# P03_DISPLAY_TOUCH.net
KiCad netlist of a schematic drawn in EasyEDA
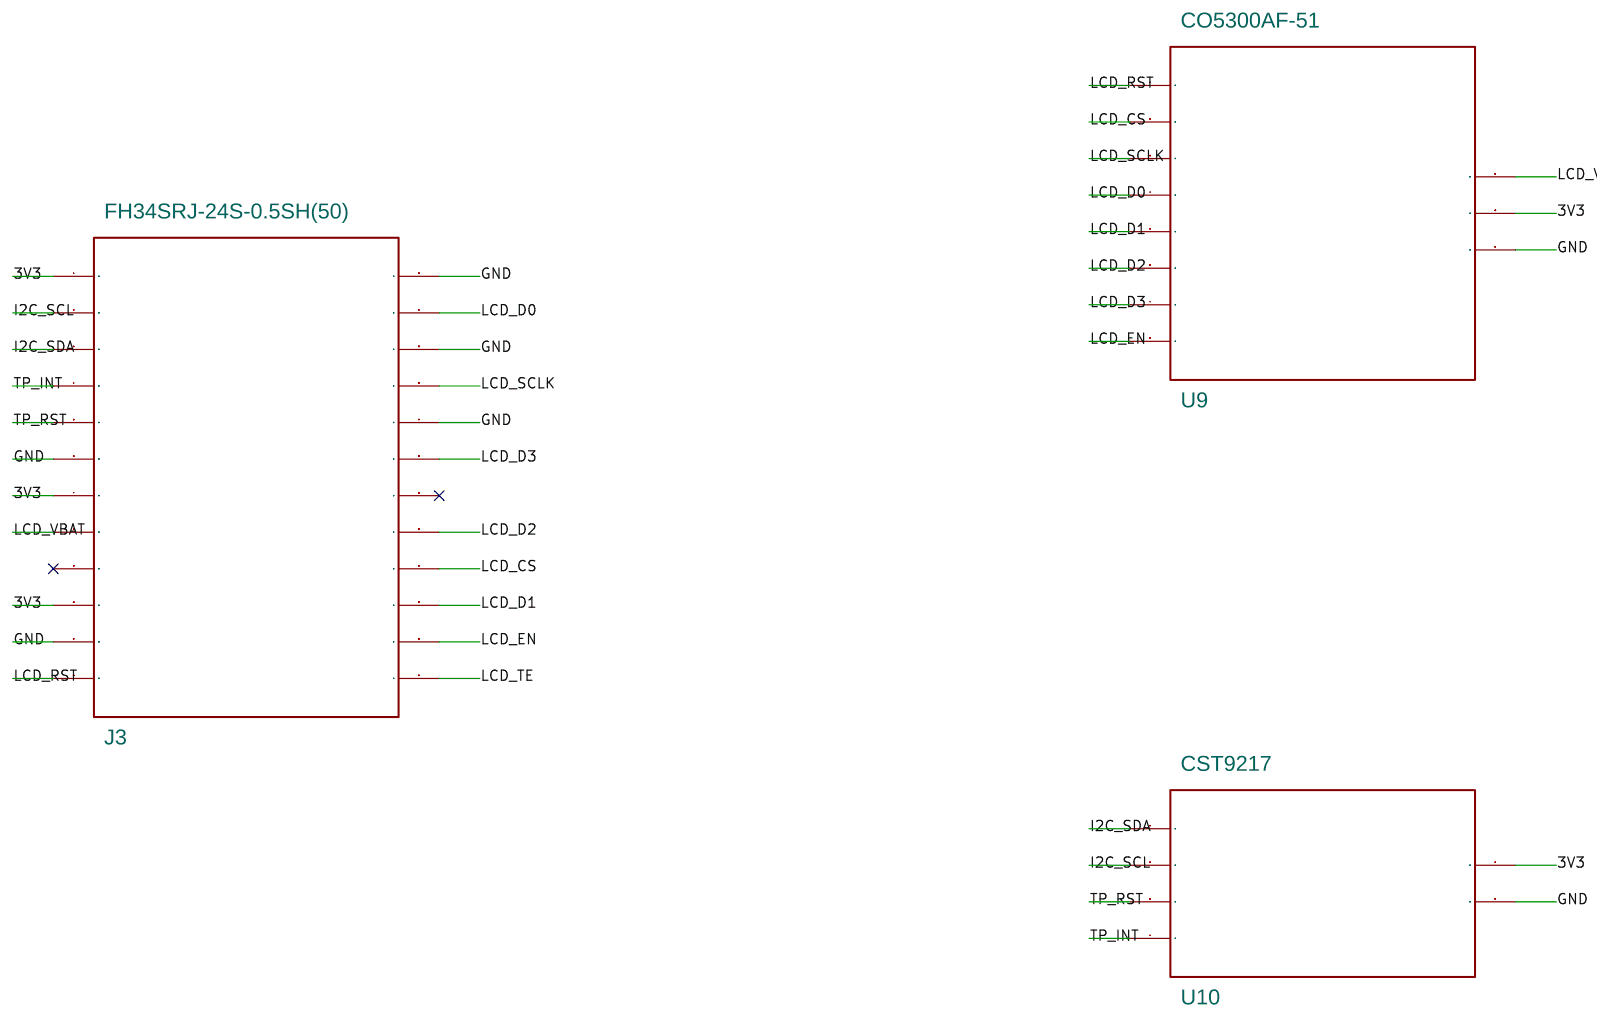
[diagram p0: schematic sheet]

(export (version "E")
  (design (tool "Eeschema 10.0.6"))
  (components
    (comp (ref "J3") (value "FH34SRJ-24S-0.5SH(50)") (libsource (lib "") (part "FPC_24P")))
    (comp (ref "U9") (value "CO5300AF-51") (libsource (lib "") (part "AMOLED_Controller")))
    (comp (ref "U10") (value "CST9217") (libsource (lib "") (part "Touch_Controller")))
  )
  (nets
    (net (code "1") (name "/3V3") (class "Default")
      (node (ref "J3") (pin "1") (pinfunction "1_1") (pintype "unspecified"))
      (node (ref "J3") (pin "10") (pinfunction "1_10") (pintype "unspecified"))
      (node (ref "J3") (pin "7") (pinfunction "1_7") (pintype "unspecified"))
      (node (ref "U10") (pin "5") (pinfunction "1_5") (pintype "unspecified"))
      (node (ref "U9") (pin "10") (pinfunction "1_10") (pintype "unspecified"))
    )
    (net (code "2") (name "/GND") (class "Default")
      (node (ref "J3") (pin "11") (pinfunction "1_11") (pintype "unspecified"))
      (node (ref "J3") (pin "13") (pinfunction "1_13") (pintype "unspecified"))
      (node (ref "J3") (pin "15") (pinfunction "1_15") (pintype "unspecified"))
      (node (ref "J3") (pin "17") (pinfunction "1_17") (pintype "unspecified"))
      (node (ref "J3") (pin "6") (pinfunction "1_6") (pintype "unspecified"))
      (node (ref "U10") (pin "6") (pinfunction "1_6") (pintype "unspecified"))
      (node (ref "U9") (pin "11") (pinfunction "1_11") (pintype "unspecified"))
    )
    (net (code "3") (name "/I2C_SCL") (class "Default")
      (node (ref "J3") (pin "2") (pinfunction "1_2") (pintype "unspecified"))
      (node (ref "U10") (pin "2") (pinfunction "1_2") (pintype "unspecified"))
    )
    (net (code "4") (name "/I2C_SDA") (class "Default")
      (node (ref "J3") (pin "3") (pinfunction "1_3") (pintype "unspecified"))
      (node (ref "U10") (pin "1") (pinfunction "1_1") (pintype "unspecified"))
    )
    (net (code "5") (name "/LCD_CS") (class "Default")
      (node (ref "J3") (pin "21") (pinfunction "1_21") (pintype "unspecified"))
      (node (ref "U9") (pin "2") (pinfunction "1_2") (pintype "unspecified"))
    )
    (net (code "6") (name "/LCD_D0") (class "Default")
      (node (ref "J3") (pin "14") (pinfunction "1_14") (pintype "unspecified"))
      (node (ref "U9") (pin "4") (pinfunction "1_4") (pintype "unspecified"))
    )
    (net (code "7") (name "/LCD_D1") (class "Default")
      (node (ref "J3") (pin "22") (pinfunction "1_22") (pintype "unspecified"))
      (node (ref "U9") (pin "5") (pinfunction "1_5") (pintype "unspecified"))
    )
    (net (code "8") (name "/LCD_D2") (class "Default")
      (node (ref "J3") (pin "20") (pinfunction "1_20") (pintype "unspecified"))
      (node (ref "U9") (pin "6") (pinfunction "1_6") (pintype "unspecified"))
    )
    (net (code "9") (name "/LCD_D3") (class "Default")
      (node (ref "J3") (pin "18") (pinfunction "1_18") (pintype "unspecified"))
      (node (ref "U9") (pin "7") (pinfunction "1_7") (pintype "unspecified"))
    )
    (net (code "10") (name "/LCD_EN") (class "Default")
      (node (ref "J3") (pin "23") (pinfunction "1_23") (pintype "unspecified"))
      (node (ref "U9") (pin "8") (pinfunction "1_8") (pintype "unspecified"))
    )
    (net (code "11") (name "/LCD_RST") (class "Default")
      (node (ref "J3") (pin "12") (pinfunction "1_12") (pintype "unspecified"))
      (node (ref "U9") (pin "1") (pinfunction "1_1") (pintype "unspecified"))
    )
    (net (code "12") (name "/LCD_SCLK") (class "Default")
      (node (ref "J3") (pin "16") (pinfunction "1_16") (pintype "unspecified"))
      (node (ref "U9") (pin "3") (pinfunction "1_3") (pintype "unspecified"))
    )
    (net (code "13") (name "/LCD_TE") (class "Default")
      (node (ref "J3") (pin "24") (pinfunction "1_24") (pintype "unspecified"))
    )
    (net (code "14") (name "/LCD_VBAT") (class "Default")
      (node (ref "J3") (pin "8") (pinfunction "1_8") (pintype "unspecified"))
      (node (ref "U9") (pin "9") (pinfunction "1_9") (pintype "unspecified"))
    )
    (net (code "15") (name "/TP_INT") (class "Default")
      (node (ref "J3") (pin "4") (pinfunction "1_4") (pintype "unspecified"))
      (node (ref "U10") (pin "4") (pinfunction "1_4") (pintype "unspecified"))
    )
    (net (code "16") (name "/TP_RST") (class "Default")
      (node (ref "J3") (pin "5") (pinfunction "1_5") (pintype "unspecified"))
      (node (ref "U10") (pin "3") (pinfunction "1_3") (pintype "unspecified"))
    )
    (net (code "17") (name "unconnected-(J3-1-Pad9)") (class "Default")
      (node (ref "J3") (pin "9") (pinfunction "1_9") (pintype "unspecified+no_connect"))
    )
    (net (code "18") (name "unconnected-(J3-1-Pad19)") (class "Default")
      (node (ref "J3") (pin "19") (pinfunction "1_19") (pintype "unspecified+no_connect"))
    )
  )
)
